# slider.net
KiCad netlist of a schematic drawn in EAGLE
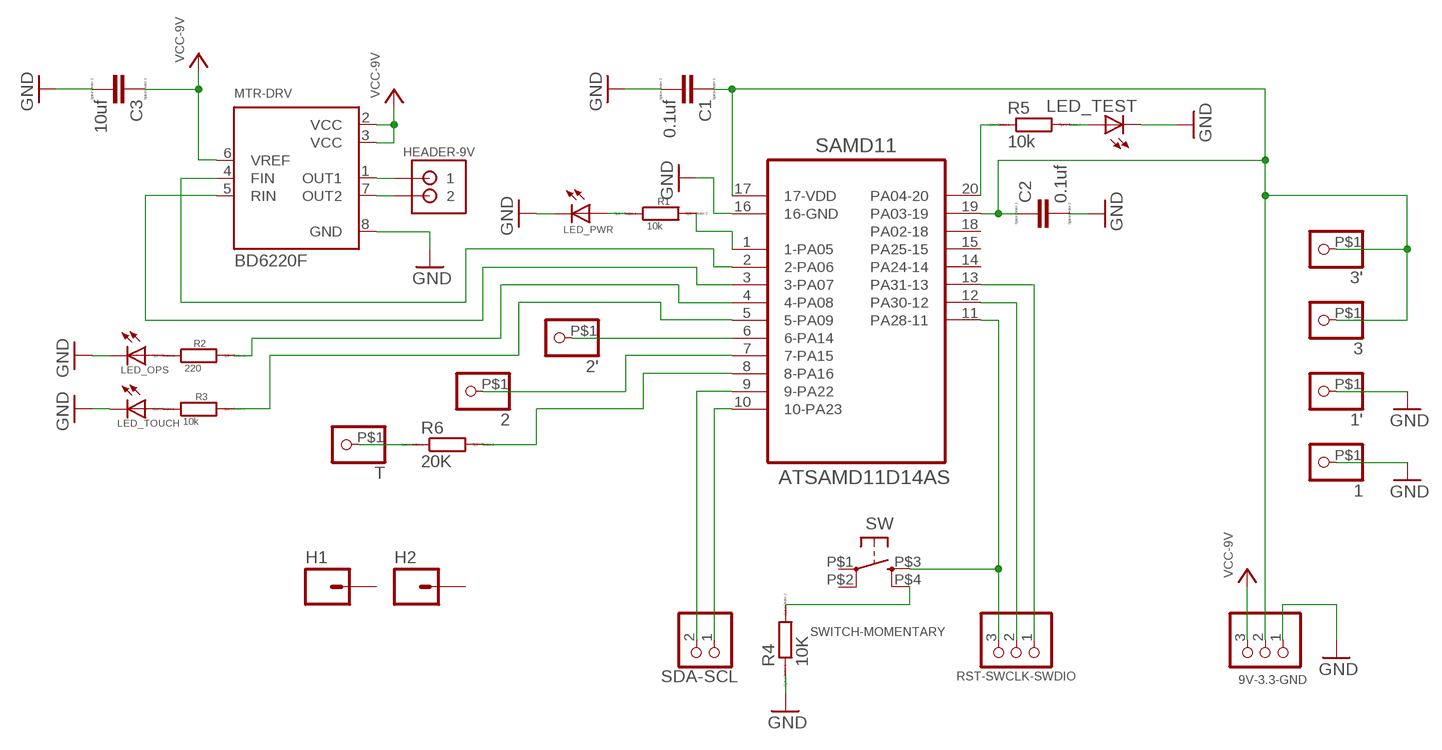
[diagram p0: schematic, sheet 1]

(export (version "E")
  (design (tool "Eeschema 10.0.6"))
  (components
    (comp (ref "1")
      (value "PINHD-1X1")
      (footprint "eagle-import:1X01")
      (libsource (lib "eagle-import") (part "PINHD-1X1"))
    )
    (comp (ref "1'")
      (value "PINHD-1X1")
      (footprint "eagle-import:1X01")
      (libsource (lib "eagle-import") (part "PINHD-1X1"))
    )
    (comp (ref "2")
      (value "PINHD-1X1")
      (footprint "eagle-import:1X01")
      (libsource (lib "eagle-import") (part "PINHD-1X1"))
    )
    (comp (ref "2'")
      (value "PINHD-1X1")
      (footprint "eagle-import:1X01")
      (libsource (lib "eagle-import") (part "PINHD-1X1"))
    )
    (comp (ref "3")
      (value "PINHD-1X1")
      (footprint "eagle-import:1X01")
      (libsource (lib "eagle-import") (part "PINHD-1X1"))
    )
    (comp (ref "3'")
      (value "PINHD-1X1")
      (footprint "eagle-import:1X01")
      (libsource (lib "eagle-import") (part "PINHD-1X1"))
    )
    (comp (ref "9V-3.3-GND")
      (value "PINHD-1X3")
      (footprint "eagle-import:1X03")
      (libsource (lib "eagle-import") (part "PINHD-1X3"))
    )
    (comp (ref "C1")
      (value "0.1uf")
      (footprint "eagle-import:C0805")
      (libsource (lib "eagle-import") (part "C"))
    )
    (comp (ref "C2")
      (value "0.1uf")
      (footprint "eagle-import:C0805")
      (libsource (lib "eagle-import") (part "C"))
    )
    (comp (ref "C3")
      (value "10uf")
      (footprint "eagle-import:C0805")
      (libsource (lib "eagle-import") (part "C"))
    )
    (comp (ref "H1")
      (value "M01PTH_2MM")
      (footprint "eagle-import:1X01_2MM")
      (libsource (lib "eagle-import") (part "M01PTH_2MM"))
    )
    (comp (ref "H2")
      (value "M01PTH_2MM")
      (footprint "eagle-import:1X01_2MM")
      (libsource (lib "eagle-import") (part "M01PTH_2MM"))
    )
    (comp (ref "HEADER-9V")
      (value "JST-PH_2-PIN_HEADER")
      (footprint "eagle-import:JST_B2B-PH_HEADER")
      (libsource (lib "eagle-import") (part "JST-PH_2-PIN_HEADER"))
    )
    (comp (ref "LED_OPS")
      (value "LEDCHIP-LED0805")
      (footprint "eagle-import:CHIP-LED0805")
      (libsource (lib "eagle-import") (part "LEDCHIP-LED0805"))
    )
    (comp (ref "LED_PWR")
      (value "LEDCHIP-LED0805")
      (footprint "eagle-import:CHIP-LED0805")
      (libsource (lib "eagle-import") (part "LEDCHIP-LED0805"))
    )
    (comp (ref "LED_TEST")
      (value "LEDCHIP-LED0805")
      (footprint "eagle-import:CHIP-LED0805")
      (libsource (lib "eagle-import") (part "LEDCHIP-LED0805"))
    )
    (comp (ref "LED_TOUCH")
      (value "LEDCHIP-LED0805")
      (footprint "eagle-import:CHIP-LED0805")
      (libsource (lib "eagle-import") (part "LEDCHIP-LED0805"))
    )
    (comp (ref "MTR-DRV")
      (value "BD6220F")
      (footprint "eagle-import:SOP8")
      (libsource (lib "eagle-import") (part "BD6220F"))
    )
    (comp (ref "R1")
      (value "10k")
      (footprint "eagle-import:R0805")
      (libsource (lib "eagle-import") (part "R"))
    )
    (comp (ref "R2")
      (value "220")
      (footprint "eagle-import:R0805")
      (libsource (lib "eagle-import") (part "R"))
    )
    (comp (ref "R3")
      (value "10k")
      (footprint "eagle-import:R0805")
      (libsource (lib "eagle-import") (part "R"))
    )
    (comp (ref "R4")
      (value "10K")
      (footprint "eagle-import:R0805")
      (libsource (lib "eagle-import") (part "R"))
    )
    (comp (ref "R5")
      (value "10k")
      (footprint "eagle-import:R0805")
      (libsource (lib "eagle-import") (part "R"))
    )
    (comp (ref "R6")
      (value "20K")
      (footprint "eagle-import:R0805")
      (libsource (lib "eagle-import") (part "R"))
    )
    (comp (ref "RST-SWCLK-SWDIO")
      (value "PINHD-1X3")
      (footprint "eagle-import:1X03")
      (libsource (lib "eagle-import") (part "PINHD-1X3"))
    )
    (comp (ref "SAMD11")
      (value "ATSAMD11D14AS")
      (footprint "eagle-import:SOIC20")
      (libsource (lib "eagle-import") (part "ATSAMD11D14AS"))
    )
    (comp (ref "SDA-SCL")
      (value "PINHD-1X2")
      (footprint "eagle-import:1X02")
      (libsource (lib "eagle-import") (part "PINHD-1X2"))
    )
    (comp (ref "SW")
      (value "SWITCH-MOMENTARY")
      (footprint "eagle-import:SWITCH-MOMENTARY")
      (libsource (lib "eagle-import") (part "SWITCH-MOMENTARY"))
    )
    (comp (ref "T")
      (value "PINHD-1X1")
      (footprint "eagle-import:1X01")
      (libsource (lib "eagle-import") (part "PINHD-1X1"))
    )
  )
  (nets
    (net (code "1") (name "GND") (class "Default")
      (node (ref "1") (pin "P$1") (pinfunction "1_P$1") (pintype "passive"))
      (node (ref "1'") (pin "P$1") (pinfunction "1_P$1") (pintype "passive"))
      (node (ref "9V-3.3-GND") (pin "1") (pinfunction "1_1") (pintype "passive"))
      (node (ref "C1") (pin "2") (pinfunction "2_2") (pintype "passive"))
      (node (ref "C2") (pin "2") (pinfunction "2_2") (pintype "passive"))
      (node (ref "C3") (pin "2") (pinfunction "2_2") (pintype "passive"))
      (node (ref "LED_OPS") (pin "C") (pinfunction "C_C") (pintype "passive"))
      (node (ref "LED_PWR") (pin "C") (pinfunction "C_C") (pintype "passive"))
      (node (ref "LED_TEST") (pin "C") (pinfunction "C_C") (pintype "passive"))
      (node (ref "LED_TOUCH") (pin "C") (pinfunction "C_C") (pintype "passive"))
      (node (ref "MTR-DRV") (pin "8") (pinfunction "GND_8") (pintype "power_in"))
      (node (ref "R4") (pin "1") (pinfunction "1_1") (pintype "passive"))
      (node (ref "SAMD11") (pin "16") (pinfunction "16-GND_16") (pintype "passive"))
    )
    (net (code "2") (name "Net-(2'-1)") (class "Default")
      (node (ref "2'") (pin "P$1") (pinfunction "1_P$1") (pintype "passive"))
      (node (ref "SAMD11") (pin "6") (pinfunction "6-PA14_6") (pintype "bidirectional"))
    )
    (net (code "3") (name "Net-(2-1)") (class "Default")
      (node (ref "2") (pin "P$1") (pinfunction "1_P$1") (pintype "passive"))
      (node (ref "SAMD11") (pin "7") (pinfunction "7-PA15_7") (pintype "bidirectional"))
    )
    (net (code "4") (name "Net-(3'-1)") (class "Default")
      (node (ref "3") (pin "P$1") (pinfunction "1_P$1") (pintype "passive"))
      (node (ref "3'") (pin "P$1") (pinfunction "1_P$1") (pintype "passive"))
      (node (ref "9V-3.3-GND") (pin "2") (pinfunction "2_2") (pintype "passive"))
      (node (ref "C1") (pin "1") (pinfunction "1_1") (pintype "passive"))
      (node (ref "C2") (pin "1") (pinfunction "1_1") (pintype "passive"))
      (node (ref "SAMD11") (pin "17") (pinfunction "17-VDD_17") (pintype "power_in"))
      (node (ref "SAMD11") (pin "19") (pinfunction "PA03-19_19") (pintype "bidirectional"))
    )
    (net (code "5") (name "Net-(HEADER-9V-1)") (class "Default")
      (node (ref "HEADER-9V") (pin "P1") (pinfunction "1_P1") (pintype "bidirectional"))
      (node (ref "MTR-DRV") (pin "1") (pinfunction "OUT1_1") (pintype "output"))
    )
    (net (code "6") (name "Net-(HEADER-9V-2)") (class "Default")
      (node (ref "HEADER-9V") (pin "P2") (pinfunction "2_P2") (pintype "bidirectional"))
      (node (ref "MTR-DRV") (pin "7") (pinfunction "OUT2_7") (pintype "output"))
    )
    (net (code "7") (name "Net-(LED_OPS-PadA)") (class "Default")
      (node (ref "LED_OPS") (pin "A") (pinfunction "A_A") (pintype "passive"))
      (node (ref "R2") (pin "1") (pinfunction "1_1") (pintype "passive"))
    )
    (net (code "8") (name "Net-(LED_PWR-PadA)") (class "Default")
      (node (ref "LED_PWR") (pin "A") (pinfunction "A_A") (pintype "passive"))
      (node (ref "R1") (pin "1") (pinfunction "1_1") (pintype "passive"))
    )
    (net (code "9") (name "Net-(LED_TEST-PadA)") (class "Default")
      (node (ref "LED_TEST") (pin "A") (pinfunction "A_A") (pintype "passive"))
      (node (ref "R5") (pin "2") (pinfunction "2_2") (pintype "passive"))
    )
    (net (code "10") (name "Net-(LED_TOUCH-PadA)") (class "Default")
      (node (ref "LED_TOUCH") (pin "A") (pinfunction "A_A") (pintype "passive"))
      (node (ref "R3") (pin "1") (pinfunction "1_1") (pintype "passive"))
    )
    (net (code "11") (name "Net-(MTR-DRV-FIN)") (class "Default")
      (node (ref "MTR-DRV") (pin "4") (pinfunction "FIN_4") (pintype "input"))
      (node (ref "SAMD11") (pin "2") (pinfunction "2-PA06_2") (pintype "bidirectional"))
    )
    (net (code "12") (name "Net-(MTR-DRV-RIN)") (class "Default")
      (node (ref "MTR-DRV") (pin "5") (pinfunction "RIN_5") (pintype "input"))
      (node (ref "SAMD11") (pin "3") (pinfunction "3-PA07_3") (pintype "bidirectional"))
    )
    (net (code "13") (name "Net-(SAMD11-1-PA05)") (class "Default")
      (node (ref "R1") (pin "2") (pinfunction "2_2") (pintype "passive"))
      (node (ref "SAMD11") (pin "1") (pinfunction "1-PA05_1") (pintype "bidirectional"))
    )
    (net (code "14") (name "Net-(SAMD11-4-PA08)") (class "Default")
      (node (ref "R2") (pin "2") (pinfunction "2_2") (pintype "passive"))
      (node (ref "SAMD11") (pin "4") (pinfunction "4-PA08_4") (pintype "bidirectional"))
    )
    (net (code "15") (name "Net-(SAMD11-5-PA09)") (class "Default")
      (node (ref "R3") (pin "2") (pinfunction "2_2") (pintype "passive"))
      (node (ref "SAMD11") (pin "5") (pinfunction "5-PA09_5") (pintype "bidirectional"))
    )
    (net (code "16") (name "Net-(SAMD11-8-PA16)") (class "Default")
      (node (ref "R6") (pin "2") (pinfunction "2_2") (pintype "passive"))
      (node (ref "SAMD11") (pin "8") (pinfunction "8-PA16_8") (pintype "bidirectional"))
    )
    (net (code "17") (name "Net-(SAMD11-9-PA22)") (class "Default")
      (node (ref "SAMD11") (pin "9") (pinfunction "9-PA22_9") (pintype "bidirectional"))
      (node (ref "SDA-SCL") (pin "2") (pinfunction "2_2") (pintype "passive"))
    )
    (net (code "18") (name "Net-(SAMD11-10-PA23)") (class "Default")
      (node (ref "SAMD11") (pin "10") (pinfunction "10-PA23_10") (pintype "bidirectional"))
      (node (ref "SDA-SCL") (pin "1") (pinfunction "1_1") (pintype "passive"))
    )
    (net (code "19") (name "Net-(SAMD11-PA04-20)") (class "Default")
      (node (ref "R5") (pin "1") (pinfunction "1_1") (pintype "passive"))
      (node (ref "SAMD11") (pin "20") (pinfunction "PA04-20_20") (pintype "bidirectional"))
    )
    (net (code "20") (name "Net-(SAMD11-PA28-11)") (class "Default")
      (node (ref "RST-SWCLK-SWDIO") (pin "3") (pinfunction "3_3") (pintype "passive"))
      (node (ref "SAMD11") (pin "11") (pinfunction "PA28-11_11") (pintype "bidirectional"))
      (node (ref "SW") (pin "P$3") (pinfunction "3_P$3") (pintype "passive"))
    )
    (net (code "21") (name "Net-(SAMD11-PA30-12)") (class "Default")
      (node (ref "RST-SWCLK-SWDIO") (pin "2") (pinfunction "2_2") (pintype "passive"))
      (node (ref "SAMD11") (pin "12") (pinfunction "PA30-12_12") (pintype "bidirectional"))
    )
    (net (code "22") (name "Net-(SAMD11-PA31-13)") (class "Default")
      (node (ref "RST-SWCLK-SWDIO") (pin "1") (pinfunction "1_1") (pintype "passive"))
      (node (ref "SAMD11") (pin "13") (pinfunction "PA31-13_13") (pintype "bidirectional"))
    )
    (net (code "23") (name "Net-(SW-4)") (class "Default")
      (node (ref "R4") (pin "2") (pinfunction "2_2") (pintype "passive"))
      (node (ref "SW") (pin "P$4") (pinfunction "4_P$4") (pintype "passive"))
    )
    (net (code "24") (name "Net-(T-1)") (class "Default")
      (node (ref "R6") (pin "1") (pinfunction "1_1") (pintype "passive"))
      (node (ref "T") (pin "P$1") (pinfunction "1_P$1") (pintype "passive"))
    )
    (net (code "25") (name "VCC-9V") (class "Default")
      (node (ref "9V-3.3-GND") (pin "3") (pinfunction "3_3") (pintype "passive"))
      (node (ref "C3") (pin "1") (pinfunction "1_1") (pintype "passive"))
      (node (ref "MTR-DRV") (pin "2") (pinfunction "VCC_2") (pintype "power_in"))
      (node (ref "MTR-DRV") (pin "3") (pinfunction "VCC_3") (pintype "power_in"))
      (node (ref "MTR-DRV") (pin "6") (pinfunction "VREF_6") (pintype "passive"))
    )
    (net (code "26") (name "unconnected-(H1-Pad1)") (class "Default")
      (node (ref "H1") (pin "1") (pinfunction "1_1") (pintype "passive"))
    )
    (net (code "27") (name "unconnected-(H2-Pad1)") (class "Default")
      (node (ref "H2") (pin "1") (pinfunction "1_1") (pintype "passive"))
    )
    (net (code "28") (name "unconnected-(SAMD11-PA02-18-Pad18)") (class "Default")
      (node (ref "SAMD11") (pin "18") (pinfunction "PA02-18_18") (pintype "bidirectional"))
    )
    (net (code "29") (name "unconnected-(SAMD11-PA24-14-Pad14)") (class "Default")
      (node (ref "SAMD11") (pin "14") (pinfunction "PA24-14_14") (pintype "bidirectional"))
    )
    (net (code "30") (name "unconnected-(SAMD11-PA25-15-Pad15)") (class "Default")
      (node (ref "SAMD11") (pin "15") (pinfunction "PA25-15_15") (pintype "bidirectional"))
    )
    (net (code "31") (name "unconnected-(SW-1-PadP$1)") (class "Default")
      (node (ref "SW") (pin "P$1") (pinfunction "1_P$1") (pintype "passive"))
    )
    (net (code "32") (name "unconnected-(SW-2-PadP$2)") (class "Default")
      (node (ref "SW") (pin "P$2") (pinfunction "2_P$2") (pintype "passive"))
    )
  )
)
